# secondary.net
KiCad netlist of a schematic drawn in EAGLE
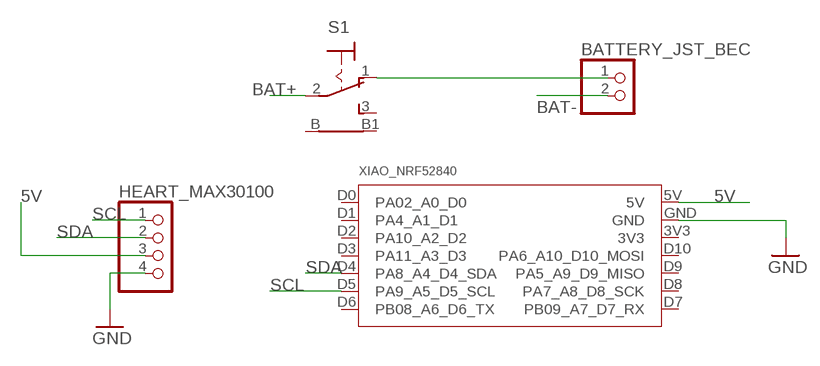
[diagram p0: schematic, sheet 1]

(export (version "E")
  (design (tool "Eeschema 10.0.6"))
  (components
    (comp (ref "BATTERY_JST_BEC")
      (value "PINHD-1X2")
      (footprint "eagle-import:1X02")
      (libsource (lib "eagle-import") (part "PINHD-1X2"))
    )
    (comp (ref "HEART_MAX30100")
      (value "PINHD-1X4")
      (footprint "eagle-import:1X04")
      (libsource (lib "eagle-import") (part "PINHD-1X4"))
    )
    (comp (ref "S1")
      (value "316-917")
      (footprint "eagle-import:316-917")
      (libsource (lib "eagle-import") (part "316-917"))
    )
    (comp (ref "XIAO_NRF52840")
      (value "SEEED-STUDIO-XIAO-SAMD21-BLE-SMD")
      (footprint "eagle-import:XIAO-NRF52840-SMD")
      (libsource (lib "eagle-import") (part "SEEED-STUDIO-XIAO-SAMD21-BLE-SMD"))
    )
  )
  (nets
    (net (code "1") (name "/5V") (class "Default")
      (node (ref "HEART_MAX30100") (pin "3") (pinfunction "3_3") (pintype "passive"))
      (node (ref "XIAO_NRF52840") (pin "5V") (pinfunction "5V_5V") (pintype "bidirectional"))
    )
    (net (code "2") (name "/BAT+") (class "Default")
      (node (ref "S1") (pin "2") (pinfunction "P_2") (pintype "passive"))
    )
    (net (code "3") (name "/BAT-") (class "Default")
      (node (ref "BATTERY_JST_BEC") (pin "2") (pinfunction "2_2") (pintype "passive"))
    )
    (net (code "4") (name "/SCL") (class "Default")
      (node (ref "HEART_MAX30100") (pin "1") (pinfunction "1_1") (pintype "passive"))
      (node (ref "XIAO_NRF52840") (pin "D5") (pinfunction "PA9_A5_D5_SCL_D5") (pintype "bidirectional"))
    )
    (net (code "5") (name "/SDA") (class "Default")
      (node (ref "HEART_MAX30100") (pin "2") (pinfunction "2_2") (pintype "passive"))
      (node (ref "XIAO_NRF52840") (pin "D4") (pinfunction "PA8_A4_D4_SDA_D4") (pintype "bidirectional"))
    )
    (net (code "6") (name "GND") (class "Default")
      (node (ref "HEART_MAX30100") (pin "4") (pinfunction "4_4") (pintype "passive"))
      (node (ref "XIAO_NRF52840") (pin "GND") (pinfunction "GND_GND") (pintype "bidirectional"))
    )
    (net (code "7") (name "Net-(S1-O)") (class "Default")
      (node (ref "BATTERY_JST_BEC") (pin "1") (pinfunction "1_1") (pintype "passive"))
      (node (ref "S1") (pin "1") (pinfunction "O_1") (pintype "passive"))
    )
    (net (code "8") (name "unconnected-(S1-PadB)") (class "Default")
      (node (ref "S1") (pin "B") (pinfunction "B_B") (pintype "passive"))
    )
    (net (code "9") (name "unconnected-(S1-PadB1)") (class "Default")
      (node (ref "S1") (pin "B1") (pinfunction "B1_B1") (pintype "passive"))
    )
    (net (code "10") (name "unconnected-(S1-S-Pad3)") (class "Default")
      (node (ref "S1") (pin "3") (pinfunction "S_3") (pintype "passive"))
    )
    (net (code "11") (name "unconnected-(XIAO_NRF52840-PA02_A0_D0-PadD0)") (class "Default")
      (node (ref "XIAO_NRF52840") (pin "D0") (pinfunction "PA02_A0_D0_D0") (pintype "bidirectional"))
    )
    (net (code "12") (name "unconnected-(XIAO_NRF52840-PA4_A1_D1-PadD1)") (class "Default")
      (node (ref "XIAO_NRF52840") (pin "D1") (pinfunction "PA4_A1_D1_D1") (pintype "bidirectional"))
    )
    (net (code "13") (name "unconnected-(XIAO_NRF52840-PA5_A9_D9_MISO-PadD9)") (class "Default")
      (node (ref "XIAO_NRF52840") (pin "D9") (pinfunction "PA5_A9_D9_MISO_D9") (pintype "bidirectional"))
    )
    (net (code "14") (name "unconnected-(XIAO_NRF52840-PA6_A10_D10_MOSI-PadD10)") (class "Default")
      (node (ref "XIAO_NRF52840") (pin "D10") (pinfunction "PA6_A10_D10_MOSI_D10") (pintype "bidirectional"))
    )
    (net (code "15") (name "unconnected-(XIAO_NRF52840-PA7_A8_D8_SCK-PadD8)") (class "Default")
      (node (ref "XIAO_NRF52840") (pin "D8") (pinfunction "PA7_A8_D8_SCK_D8") (pintype "bidirectional"))
    )
    (net (code "16") (name "unconnected-(XIAO_NRF52840-PA10_A2_D2-PadD2)") (class "Default")
      (node (ref "XIAO_NRF52840") (pin "D2") (pinfunction "PA10_A2_D2_D2") (pintype "bidirectional"))
    )
    (net (code "17") (name "unconnected-(XIAO_NRF52840-PA11_A3_D3-PadD3)") (class "Default")
      (node (ref "XIAO_NRF52840") (pin "D3") (pinfunction "PA11_A3_D3_D3") (pintype "bidirectional"))
    )
    (net (code "18") (name "unconnected-(XIAO_NRF52840-PB08_A6_D6_TX-PadD6)") (class "Default")
      (node (ref "XIAO_NRF52840") (pin "D6") (pinfunction "PB08_A6_D6_TX_D6") (pintype "bidirectional"))
    )
    (net (code "19") (name "unconnected-(XIAO_NRF52840-PB09_A7_D7_RX-PadD7)") (class "Default")
      (node (ref "XIAO_NRF52840") (pin "D7") (pinfunction "PB09_A7_D7_RX_D7") (pintype "bidirectional"))
    )
    (net (code "20") (name "unconnected-(XIAO_NRF52840-Pad3V3)") (class "Default")
      (node (ref "XIAO_NRF52840") (pin "3V3") (pinfunction "3V3_3V3") (pintype "bidirectional"))
    )
  )
)
